# Lamp_Logic_Board_40_BRAIN.net
KiCad netlist of a schematic drawn in EAGLE
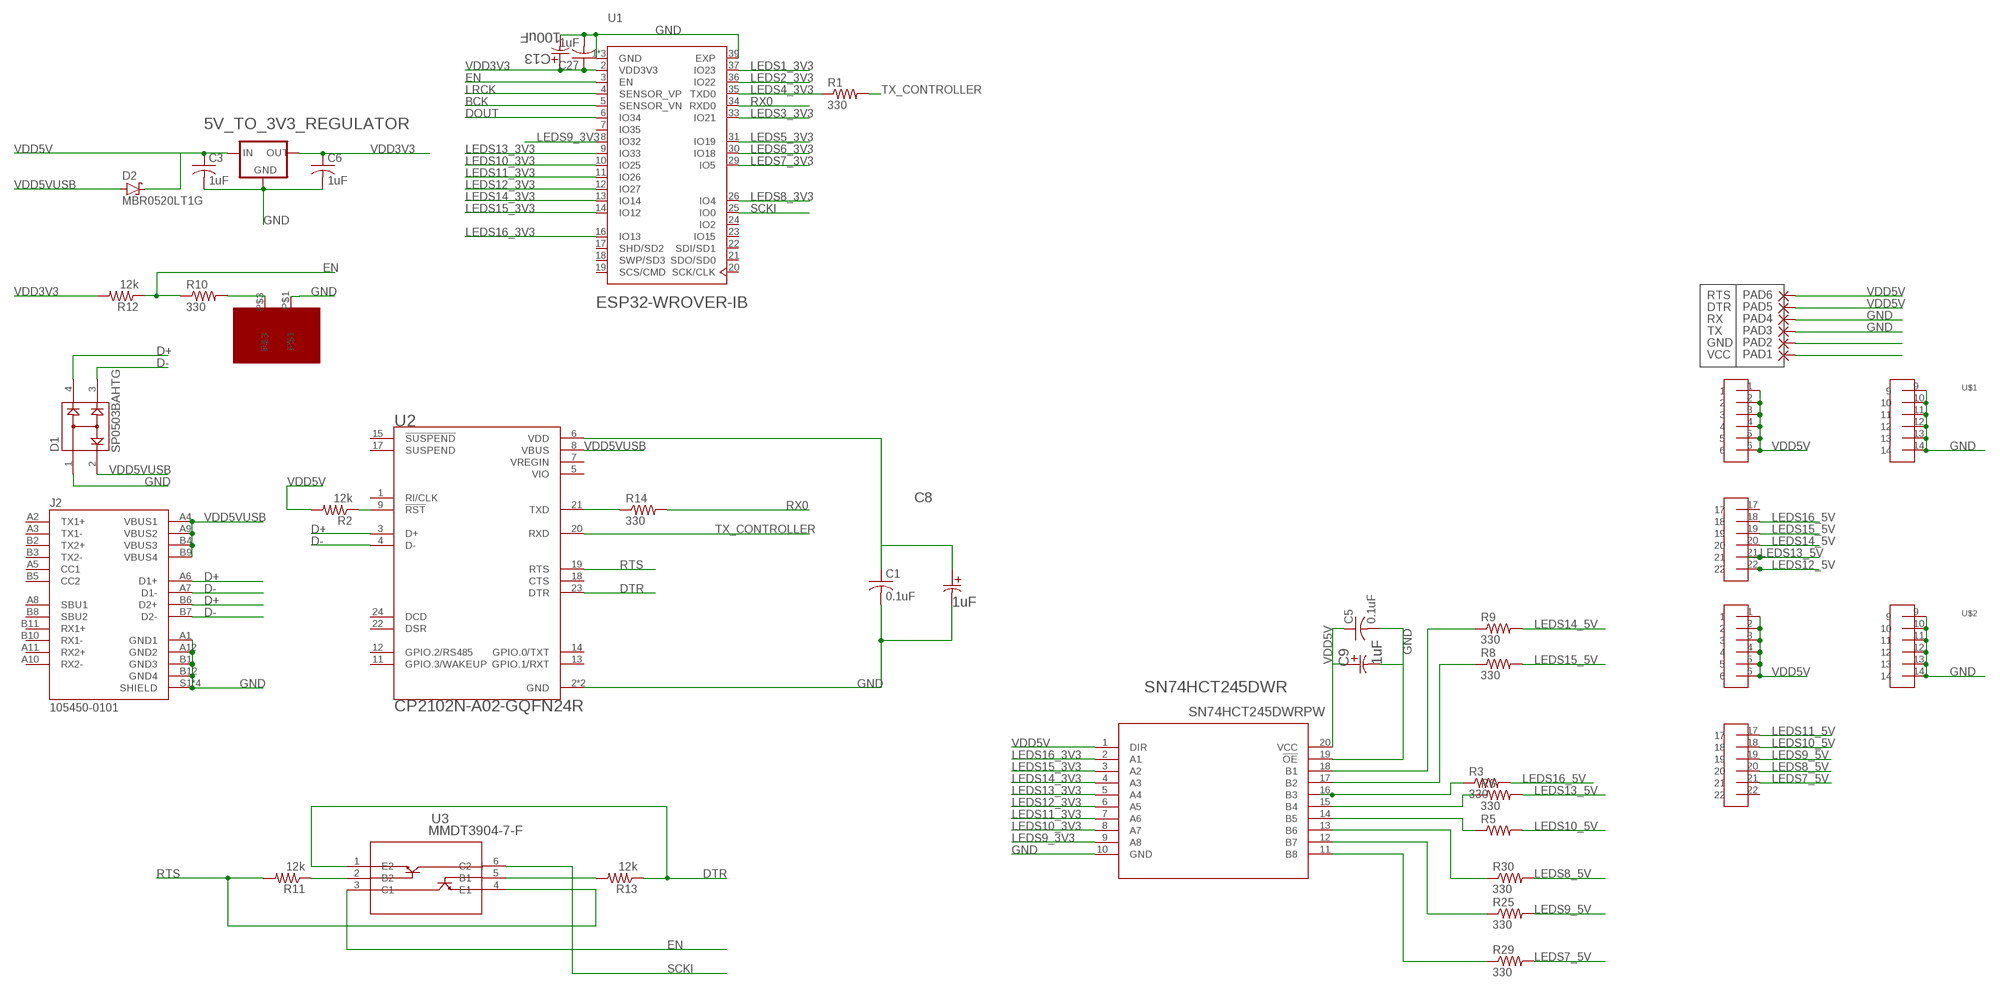
[diagram p0: schematic, sheet 1]

(export (version "E")
  (design (tool "Eeschema 10.0.6"))
  (components
    (comp (ref "5V_TO_3V3_REGULATOR")
      (value "LM1117MP-1.8")
      (footprint "eagle-import:SOT223")
      (fields (field (name "MF") "Texas Instruments"))
      (libsource (lib "eagle-import") (part "LM1117?-MP1.8"))
    )
    (comp (ref "C1")
      (value "0.1uF")
      (footprint "eagle-import:C0402")
      (libsource (lib "eagle-import") (part "C-USC0402"))
    )
    (comp (ref "C3")
      (value "1uF")
      (footprint "eagle-import:C0402")
      (libsource (lib "eagle-import") (part "C-USC0402"))
    )
    (comp (ref "C5")
      (value "0.1uF")
      (footprint "eagle-import:C0805")
      (libsource (lib "eagle-import") (part "C-USC0805"))
    )
    (comp (ref "C6")
      (value "1uF")
      (footprint "eagle-import:C0402")
      (libsource (lib "eagle-import") (part "C-USC0402"))
    )
    (comp (ref "C8")
      (value "1uF")
      (footprint "eagle-import:CAP_EEFC_B")
      (fields (field (name "MANUFACTURER_PART_NUMBER") "EEEFC1V1R0R"))
      (libsource (lib "eagle-import") (part "EEEFC1V1R0R"))
    )
    (comp (ref "C9")
      (value "1uF")
      (footprint "eagle-import:CAP_EEFC_B")
      (fields (field (name "MANUFACTURER_PART_NUMBER") "EEEFC1V1R0R"))
      (libsource (lib "eagle-import") (part "EEEFC1V1R0R"))
    )
    (comp (ref "C13")
      (value "100uF")
      (footprint "eagle-import:CAP_EEFC_B")
      (fields (field (name "MANUFACTURER_PART_NUMBER") "EEEFC1V1R0R"))
      (libsource (lib "eagle-import") (part "EEEFC1V1R0R"))
    )
    (comp (ref "C27")
      (value "1uF")
      (footprint "eagle-import:C0402")
      (libsource (lib "eagle-import") (part "C-USC0402"))
    )
    (comp (ref "D1")
      (value "SP0503BAHTG")
      (footprint "eagle-import:SOT143")
      (fields (field (name "DIGI-KEY_PART_NUMBER") "F2715CT-ND") (field (name "MF") "Littelfuse Inc."))
      (libsource (lib "eagle-import") (part "SP0503BAHTG"))
    )
    (comp (ref "D2")
      (value "MBR0520LT1G")
      (footprint "eagle-import:SOD-123")
      (fields
        (field (name "DIGIKEY_PART_NUMBER") "MBR0520LT1GOSTR-ND")
        (field (name "MANUFACTURER") "ON Semiconductor")
        (field (name "CREATED_BY") "PCBLayout.com")
      )
      (libsource (lib "eagle-import") (part "MBR0520LT1G"))
    )
    (comp (ref "J2")
      (value "105450-0101")
      (footprint "eagle-import:MOLEX_105450-0101")
      (fields
        (field (name "DIGI-KEY_PART_NUMBER") "WM12856CT-ND")
        (field (name "MF") "Molex")
        (field (name "MP") "1054500101")
      )
      (libsource (lib "eagle-import") (part "105450-0101"))
    )
    (comp (ref "PAD1")
      (value "VCC")
      (footprint "eagle-import:SMD1,27-2,54")
      (libsource (lib "eagle-import") (part "WIREPADSMD1,27-254"))
    )
    (comp (ref "PAD2")
      (value "GND")
      (footprint "eagle-import:SMD1,27-2,54")
      (libsource (lib "eagle-import") (part "WIREPADSMD1,27-254"))
    )
    (comp (ref "PAD3")
      (value "TX")
      (footprint "eagle-import:SMD1,27-2,54")
      (libsource (lib "eagle-import") (part "WIREPADSMD1,27-254"))
    )
    (comp (ref "PAD4")
      (value "RX")
      (footprint "eagle-import:SMD1,27-2,54")
      (libsource (lib "eagle-import") (part "WIREPADSMD1,27-254"))
    )
    (comp (ref "PAD5")
      (value "DTR")
      (footprint "eagle-import:SMD1,27-2,54")
      (libsource (lib "eagle-import") (part "WIREPADSMD1,27-254"))
    )
    (comp (ref "PAD6")
      (value "RTS")
      (footprint "eagle-import:SMD1,27-2,54")
      (libsource (lib "eagle-import") (part "WIREPADSMD1,27-254"))
    )
    (comp (ref "R1")
      (value "330")
      (footprint "eagle-import:RES_0603")
      (fields
        (field (name "DIGIKEY_PART_NUMBER") "311-0.0GRTR-ND")
        (field (name "MANUFACTURER") "Yageo")
        (field (name "MPN") "RC0603JR-070RL")
        (field (name "CREATED_BY") "PCBLayout.com")
      )
      (libsource (lib "eagle-import") (part "RC0603JR-070RL"))
    )
    (comp (ref "R2")
      (value "12k")
      (footprint "eagle-import:RES_0603")
      (fields
        (field (name "DIGIKEY_PART_NUMBER") "311-0.0GRTR-ND")
        (field (name "MANUFACTURER") "Yageo")
        (field (name "MPN") "RC0603JR-070RL")
        (field (name "CREATED_BY") "PCBLayout.com")
      )
      (libsource (lib "eagle-import") (part "RC0603JR-070RL"))
    )
    (comp (ref "R3")
      (value "330")
      (footprint "eagle-import:RES_0603")
      (fields
        (field (name "DIGIKEY_PART_NUMBER") "311-0.0GRTR-ND")
        (field (name "MANUFACTURER") "Yageo")
        (field (name "MPN") "RC0603JR-070RL")
        (field (name "CREATED_BY") "PCBLayout.com")
      )
      (libsource (lib "eagle-import") (part "RC0603JR-070RL"))
    )
    (comp (ref "R5")
      (value "330")
      (footprint "eagle-import:RES_0603")
      (fields
        (field (name "DIGIKEY_PART_NUMBER") "311-0.0GRTR-ND")
        (field (name "MANUFACTURER") "Yageo")
        (field (name "MPN") "RC0603JR-070RL")
        (field (name "CREATED_BY") "PCBLayout.com")
      )
      (libsource (lib "eagle-import") (part "RC0603JR-070RL"))
    )
    (comp (ref "R6")
      (value "330")
      (footprint "eagle-import:RES_0603")
      (fields
        (field (name "DIGIKEY_PART_NUMBER") "311-0.0GRTR-ND")
        (field (name "MANUFACTURER") "Yageo")
        (field (name "MPN") "RC0603JR-070RL")
        (field (name "CREATED_BY") "PCBLayout.com")
      )
      (libsource (lib "eagle-import") (part "RC0603JR-070RL"))
    )
    (comp (ref "R8")
      (value "330")
      (footprint "eagle-import:RES_0603")
      (fields
        (field (name "DIGIKEY_PART_NUMBER") "311-0.0GRTR-ND")
        (field (name "MANUFACTURER") "Yageo")
        (field (name "MPN") "RC0603JR-070RL")
        (field (name "CREATED_BY") "PCBLayout.com")
      )
      (libsource (lib "eagle-import") (part "RC0603JR-070RL"))
    )
    (comp (ref "R9")
      (value "330")
      (footprint "eagle-import:RES_0603")
      (fields
        (field (name "DIGIKEY_PART_NUMBER") "311-0.0GRTR-ND")
        (field (name "MANUFACTURER") "Yageo")
        (field (name "MPN") "RC0603JR-070RL")
        (field (name "CREATED_BY") "PCBLayout.com")
      )
      (libsource (lib "eagle-import") (part "RC0603JR-070RL"))
    )
    (comp (ref "R10")
      (value "330")
      (footprint "eagle-import:RES_0603")
      (fields
        (field (name "DIGIKEY_PART_NUMBER") "311-0.0GRTR-ND")
        (field (name "MANUFACTURER") "Yageo")
        (field (name "MPN") "RC0603JR-070RL")
        (field (name "CREATED_BY") "PCBLayout.com")
      )
      (libsource (lib "eagle-import") (part "RC0603JR-070RL"))
    )
    (comp (ref "R11")
      (value "12k")
      (footprint "eagle-import:RES_0603")
      (fields
        (field (name "DIGIKEY_PART_NUMBER") "311-0.0GRTR-ND")
        (field (name "MANUFACTURER") "Yageo")
        (field (name "MPN") "RC0603JR-070RL")
        (field (name "CREATED_BY") "PCBLayout.com")
      )
      (libsource (lib "eagle-import") (part "RC0603JR-070RL"))
    )
    (comp (ref "R12")
      (value "12k")
      (footprint "eagle-import:RES_0603")
      (fields
        (field (name "DIGIKEY_PART_NUMBER") "311-0.0GRTR-ND")
        (field (name "MANUFACTURER") "Yageo")
        (field (name "MPN") "RC0603JR-070RL")
        (field (name "CREATED_BY") "PCBLayout.com")
      )
      (libsource (lib "eagle-import") (part "RC0603JR-070RL"))
    )
    (comp (ref "R13")
      (value "12k")
      (footprint "eagle-import:RES_0603")
      (fields
        (field (name "DIGIKEY_PART_NUMBER") "311-0.0GRTR-ND")
        (field (name "MANUFACTURER") "Yageo")
        (field (name "MPN") "RC0603JR-070RL")
        (field (name "CREATED_BY") "PCBLayout.com")
      )
      (libsource (lib "eagle-import") (part "RC0603JR-070RL"))
    )
    (comp (ref "R14")
      (value "330")
      (footprint "eagle-import:RES_0603")
      (fields
        (field (name "DIGIKEY_PART_NUMBER") "311-0.0GRTR-ND")
        (field (name "MANUFACTURER") "Yageo")
        (field (name "MPN") "RC0603JR-070RL")
        (field (name "CREATED_BY") "PCBLayout.com")
      )
      (libsource (lib "eagle-import") (part "RC0603JR-070RL"))
    )
    (comp (ref "R25")
      (value "330")
      (footprint "eagle-import:RES_0603")
      (fields
        (field (name "DIGIKEY_PART_NUMBER") "311-0.0GRTR-ND")
        (field (name "MANUFACTURER") "Yageo")
        (field (name "MPN") "RC0603JR-070RL")
        (field (name "CREATED_BY") "PCBLayout.com")
      )
      (libsource (lib "eagle-import") (part "RC0603JR-070RL"))
    )
    (comp (ref "R29")
      (value "330")
      (footprint "eagle-import:RES_0603")
      (fields
        (field (name "DIGIKEY_PART_NUMBER") "311-0.0GRTR-ND")
        (field (name "MANUFACTURER") "Yageo")
        (field (name "MPN") "RC0603JR-070RL")
        (field (name "CREATED_BY") "PCBLayout.com")
      )
      (libsource (lib "eagle-import") (part "RC0603JR-070RL"))
    )
    (comp (ref "R30")
      (value "330")
      (footprint "eagle-import:RES_0603")
      (fields
        (field (name "DIGIKEY_PART_NUMBER") "311-0.0GRTR-ND")
        (field (name "MANUFACTURER") "Yageo")
        (field (name "MPN") "RC0603JR-070RL")
        (field (name "CREATED_BY") "PCBLayout.com")
      )
      (libsource (lib "eagle-import") (part "RC0603JR-070RL"))
    )
    (comp (ref "SN74HCT245DWR")
      (value "SN74HCT245DWRPW")
      (footprint "eagle-import:PW")
      (libsource (lib "eagle-import") (part "SN74HCT245DWRPW"))
    )
    (comp (ref "U$1")
      (value "3X8PINHEAD")
      (footprint "eagle-import:3X8PINHEAD")
      (libsource (lib "eagle-import") (part "3X8PINHEAD"))
    )
    (comp (ref "U$2")
      (value "3X8PINHEAD")
      (footprint "eagle-import:3X8PINHEAD")
      (libsource (lib "eagle-import") (part "3X8PINHEAD"))
    )
    (comp (ref "U$7")
      (value "TL1014BF160QG")
      (footprint "eagle-import:TL1014BF160QG")
      (libsource (lib "eagle-import") (part "TL1014BF160QG"))
    )
    (comp (ref "U1")
      (value "ESP32-WROVER-IB")
      (footprint "eagle-import:XCVR_ESP32-WROVER-I")
      (fields (field (name "MF") "Espressif Systems") (field (name "MP") "ESP32-WROVER-I"))
      (libsource (lib "eagle-import") (part "ESP32-WROVER-I"))
    )
    (comp (ref "U2")
      (value "CP2102N-A02-GQFN24R")
      (footprint "eagle-import:SILABS_CP2102N-A02-GQFN24R")
      (libsource (lib "eagle-import") (part "CP2102N-A02-GQFN24R"))
    )
    (comp (ref "U3")
      (value "MMDT3904-7-F")
      (footprint "eagle-import:SOT-363")
      (fields (field (name "MANUFACTURER_PART_NUMBER") "MMDT39047F"))
      (libsource (lib "eagle-import") (part "MMDT3904-7-F"))
    )
  )
  (nets
    (net (code "1") (name "BCK") (class "Default")
      (node (ref "U1") (pin "5") (pinfunction "SENSOR_VN_5") (pintype "input"))
    )
    (net (code "2") (name "D+") (class "Default")
      (node (ref "D1") (pin "4") (pinfunction "4_4") (pintype "passive"))
      (node (ref "J2") (pin "A6") (pinfunction "D1+_A6") (pintype "passive"))
      (node (ref "J2") (pin "B6") (pinfunction "D2+_B6") (pintype "passive"))
      (node (ref "U2") (pin "3") (pinfunction "D+_3") (pintype "bidirectional"))
    )
    (net (code "3") (name "D-") (class "Default")
      (node (ref "D1") (pin "3") (pinfunction "3_3") (pintype "passive"))
      (node (ref "J2") (pin "A7") (pinfunction "D1-_A7") (pintype "passive"))
      (node (ref "J2") (pin "B7") (pinfunction "D2-_B7") (pintype "passive"))
      (node (ref "U2") (pin "4") (pinfunction "D-_4") (pintype "bidirectional"))
    )
    (net (code "4") (name "DOUT") (class "Default")
      (node (ref "U1") (pin "6") (pinfunction "IO34_6") (pintype "input"))
    )
    (net (code "5") (name "DTR") (class "Default")
      (node (ref "R13") (pin "1") (pinfunction "1_1") (pintype "passive"))
      (node (ref "U2") (pin "23") (pinfunction "DTR_23") (pintype "bidirectional"))
      (node (ref "U3") (pin "1") (pinfunction "E2_1") (pintype "passive"))
    )
    (net (code "6") (name "EN") (class "Default")
      (node (ref "R10") (pin "1") (pinfunction "1_1") (pintype "passive"))
      (node (ref "R12") (pin "1") (pinfunction "1_1") (pintype "passive"))
      (node (ref "U1") (pin "3") (pinfunction "EN_3") (pintype "input"))
      (node (ref "U3") (pin "3") (pinfunction "C1_3") (pintype "passive"))
    )
    (net (code "7") (name "GND") (class "Default")
      (node (ref "5V_TO_3V3_REGULATOR") (pin "1") (pinfunction "GND_1") (pintype "input"))
      (node (ref "C1") (pin "2") (pinfunction "2_2") (pintype "passive"))
      (node (ref "C13") (pin "2") (pinfunction "2_2") (pintype "passive"))
      (node (ref "C27") (pin "2") (pinfunction "2_2") (pintype "passive"))
      (node (ref "C3") (pin "2") (pinfunction "2_2") (pintype "passive"))
      (node (ref "C5") (pin "2") (pinfunction "2_2") (pintype "passive"))
      (node (ref "C6") (pin "2") (pinfunction "2_2") (pintype "passive"))
      (node (ref "C8") (pin "2") (pinfunction "2_2") (pintype "passive"))
      (node (ref "C9") (pin "2") (pinfunction "2_2") (pintype "passive"))
      (node (ref "D1") (pin "1") (pinfunction "1_1") (pintype "passive"))
      (node (ref "J2") (pin "A1") (pinfunction "GND1_A1") (pintype "passive"))
      (node (ref "J2") (pin "A12") (pinfunction "GND2_A12") (pintype "passive"))
      (node (ref "J2") (pin "B1") (pinfunction "GND3_B1") (pintype "passive"))
      (node (ref "J2") (pin "B12") (pinfunction "GND4_B12") (pintype "passive"))
      (node (ref "J2") (pin "S1") (pinfunction "SHIELD_S1") (pintype "passive"))
      (node (ref "J2") (pin "S2") (pinfunction "SHIELD_S2") (pintype "passive"))
      (node (ref "J2") (pin "S3") (pinfunction "SHIELD_S3") (pintype "passive"))
      (node (ref "J2") (pin "S4") (pinfunction "SHIELD_S4") (pintype "passive"))
      (node (ref "PAD3") (pin "1") (pinfunction "P_1") (pintype "passive"))
      (node (ref "PAD4") (pin "1") (pinfunction "P_1") (pintype "passive"))
      (node (ref "SN74HCT245DWR") (pin "10") (pinfunction "GND_10") (pintype "power_in"))
      (node (ref "SN74HCT245DWR") (pin "19") (pinfunction "~{OE}_19") (pintype "input"))
      (node (ref "U$1") (pin "10") (pinfunction "10_10") (pintype "bidirectional"))
      (node (ref "U$1") (pin "11") (pinfunction "11_11") (pintype "bidirectional"))
      (node (ref "U$1") (pin "12") (pinfunction "12_12") (pintype "bidirectional"))
      (node (ref "U$1") (pin "13") (pinfunction "13_13") (pintype "bidirectional"))
      (node (ref "U$1") (pin "14") (pinfunction "14_14") (pintype "bidirectional"))
      (node (ref "U$1") (pin "9") (pinfunction "9_9") (pintype "bidirectional"))
      (node (ref "U$2") (pin "10") (pinfunction "10_10") (pintype "bidirectional"))
      (node (ref "U$2") (pin "11") (pinfunction "11_11") (pintype "bidirectional"))
      (node (ref "U$2") (pin "12") (pinfunction "12_12") (pintype "bidirectional"))
      (node (ref "U$2") (pin "13") (pinfunction "13_13") (pintype "bidirectional"))
      (node (ref "U$2") (pin "14") (pinfunction "14_14") (pintype "bidirectional"))
      (node (ref "U$2") (pin "9") (pinfunction "9_9") (pintype "bidirectional"))
      (node (ref "U$7") (pin "P$1") (pinfunction "P$1_P$1") (pintype "bidirectional"))
      (node (ref "U1") (pin "1") (pinfunction "GND_1") (pintype "power_in"))
      (node (ref "U1") (pin "15") (pinfunction "GND_15") (pintype "power_in"))
      (node (ref "U1") (pin "38") (pinfunction "GND_38") (pintype "power_in"))
      (node (ref "U1") (pin "39") (pinfunction "EXP_39") (pintype "power_in"))
      (node (ref "U2") (pin "2") (pinfunction "GND_2") (pintype "power_in"))
      (node (ref "U2") (pin "25") (pinfunction "GND_25") (pintype "power_in"))
    )
    (net (code "8") (name "LEDS1_3V3") (class "Default")
      (node (ref "U1") (pin "37") (pinfunction "IO23_37") (pintype "bidirectional"))
    )
    (net (code "9") (name "LEDS2_3V3") (class "Default")
      (node (ref "U1") (pin "36") (pinfunction "IO22_36") (pintype "bidirectional"))
    )
    (net (code "10") (name "LEDS3_3V3") (class "Default")
      (node (ref "U1") (pin "33") (pinfunction "IO21_33") (pintype "bidirectional"))
    )
    (net (code "11") (name "LEDS4_3V3") (class "Default")
      (node (ref "R1") (pin "1") (pinfunction "1_1") (pintype "passive"))
      (node (ref "U1") (pin "35") (pinfunction "TXD0_35") (pintype "bidirectional"))
    )
    (net (code "12") (name "LEDS5_3V3") (class "Default")
      (node (ref "U1") (pin "31") (pinfunction "IO19_31") (pintype "bidirectional"))
    )
    (net (code "13") (name "LEDS6_3V3") (class "Default")
      (node (ref "U1") (pin "30") (pinfunction "IO18_30") (pintype "bidirectional"))
    )
    (net (code "14") (name "LEDS7_3V3") (class "Default")
      (node (ref "U1") (pin "29") (pinfunction "IO5_29") (pintype "bidirectional"))
    )
    (net (code "15") (name "LEDS7_5V") (class "Default")
      (node (ref "R29") (pin "2") (pinfunction "2_2") (pintype "passive"))
      (node (ref "U$2") (pin "21") (pinfunction "21_21") (pintype "bidirectional"))
    )
    (net (code "16") (name "LEDS8_3V3") (class "Default")
      (node (ref "U1") (pin "26") (pinfunction "IO4_26") (pintype "bidirectional"))
    )
    (net (code "17") (name "LEDS8_5V") (class "Default")
      (node (ref "R30") (pin "2") (pinfunction "2_2") (pintype "passive"))
      (node (ref "U$2") (pin "20") (pinfunction "20_20") (pintype "bidirectional"))
    )
    (net (code "18") (name "LEDS9_3V3") (class "Default")
      (node (ref "SN74HCT245DWR") (pin "9") (pinfunction "A8_9") (pintype "bidirectional"))
      (node (ref "U1") (pin "8") (pinfunction "IO32_8") (pintype "bidirectional"))
    )
    (net (code "19") (name "LEDS9_5V") (class "Default")
      (node (ref "R25") (pin "2") (pinfunction "2_2") (pintype "passive"))
      (node (ref "U$2") (pin "19") (pinfunction "19_19") (pintype "bidirectional"))
    )
    (net (code "20") (name "LEDS10_3V3") (class "Default")
      (node (ref "SN74HCT245DWR") (pin "8") (pinfunction "A7_8") (pintype "bidirectional"))
      (node (ref "U1") (pin "10") (pinfunction "IO25_10") (pintype "bidirectional"))
    )
    (net (code "21") (name "LEDS10_5V") (class "Default")
      (node (ref "R5") (pin "2") (pinfunction "2_2") (pintype "passive"))
      (node (ref "U$2") (pin "18") (pinfunction "18_18") (pintype "bidirectional"))
    )
    (net (code "22") (name "LEDS11_3V3") (class "Default")
      (node (ref "SN74HCT245DWR") (pin "7") (pinfunction "A6_7") (pintype "bidirectional"))
      (node (ref "U1") (pin "11") (pinfunction "IO26_11") (pintype "bidirectional"))
    )
    (net (code "23") (name "LEDS11_5V") (class "Default")
      (node (ref "U$2") (pin "17") (pinfunction "17_17") (pintype "bidirectional"))
    )
    (net (code "24") (name "LEDS12_3V3") (class "Default")
      (node (ref "SN74HCT245DWR") (pin "6") (pinfunction "A5_6") (pintype "bidirectional"))
      (node (ref "U1") (pin "12") (pinfunction "IO27_12") (pintype "bidirectional"))
    )
    (net (code "25") (name "LEDS12_5V") (class "Default")
      (node (ref "U$1") (pin "22") (pinfunction "22_22") (pintype "bidirectional"))
    )
    (net (code "26") (name "LEDS13_3V3") (class "Default")
      (node (ref "SN74HCT245DWR") (pin "5") (pinfunction "A4_5") (pintype "bidirectional"))
      (node (ref "U1") (pin "9") (pinfunction "IO33_9") (pintype "bidirectional"))
    )
    (net (code "27") (name "LEDS13_5V") (class "Default")
      (node (ref "R6") (pin "2") (pinfunction "2_2") (pintype "passive"))
      (node (ref "U$1") (pin "21") (pinfunction "21_21") (pintype "bidirectional"))
    )
    (net (code "28") (name "LEDS14_3V3") (class "Default")
      (node (ref "SN74HCT245DWR") (pin "4") (pinfunction "A3_4") (pintype "bidirectional"))
      (node (ref "U1") (pin "13") (pinfunction "IO14_13") (pintype "bidirectional"))
    )
    (net (code "29") (name "LEDS14_5V") (class "Default")
      (node (ref "R9") (pin "2") (pinfunction "2_2") (pintype "passive"))
      (node (ref "U$1") (pin "20") (pinfunction "20_20") (pintype "bidirectional"))
    )
    (net (code "30") (name "LEDS15_3V3") (class "Default")
      (node (ref "SN74HCT245DWR") (pin "3") (pinfunction "A2_3") (pintype "bidirectional"))
      (node (ref "U1") (pin "14") (pinfunction "IO12_14") (pintype "bidirectional"))
    )
    (net (code "31") (name "LEDS15_5V") (class "Default")
      (node (ref "R8") (pin "2") (pinfunction "2_2") (pintype "passive"))
      (node (ref "U$1") (pin "19") (pinfunction "19_19") (pintype "bidirectional"))
    )
    (net (code "32") (name "LEDS16_3V3") (class "Default")
      (node (ref "SN74HCT245DWR") (pin "2") (pinfunction "A1_2") (pintype "bidirectional"))
      (node (ref "U1") (pin "16") (pinfunction "IO13_16") (pintype "bidirectional"))
    )
    (net (code "33") (name "LEDS16_5V") (class "Default")
      (node (ref "R3") (pin "2") (pinfunction "2_2") (pintype "passive"))
      (node (ref "U$1") (pin "18") (pinfunction "18_18") (pintype "bidirectional"))
    )
    (net (code "34") (name "LRCK") (class "Default")
      (node (ref "U1") (pin "4") (pinfunction "SENSOR_VP_4") (pintype "input"))
    )
    (net (code "35") (name "Net-(R10-Pad2)") (class "Default")
      (node (ref "R10") (pin "2") (pinfunction "2_2") (pintype "passive"))
      (node (ref "U$7") (pin "P$3") (pinfunction "P$3_P$3") (pintype "bidirectional"))
    )
    (net (code "36") (name "Net-(SN74HCT245DWR-B1)") (class "Default")
      (node (ref "R9") (pin "1") (pinfunction "1_1") (pintype "passive"))
      (node (ref "SN74HCT245DWR") (pin "18") (pinfunction "B1_18") (pintype "bidirectional"))
    )
    (net (code "37") (name "Net-(SN74HCT245DWR-B2)") (class "Default")
      (node (ref "R8") (pin "1") (pinfunction "1_1") (pintype "passive"))
      (node (ref "SN74HCT245DWR") (pin "17") (pinfunction "B2_17") (pintype "bidirectional"))
    )
    (net (code "38") (name "Net-(SN74HCT245DWR-B3)") (class "Default")
      (node (ref "R3") (pin "1") (pinfunction "1_1") (pintype "passive"))
      (node (ref "SN74HCT245DWR") (pin "16") (pinfunction "B3_16") (pintype "bidirectional"))
    )
    (net (code "39") (name "Net-(SN74HCT245DWR-B4)") (class "Default")
      (node (ref "R6") (pin "1") (pinfunction "1_1") (pintype "passive"))
      (node (ref "SN74HCT245DWR") (pin "15") (pinfunction "B4_15") (pintype "bidirectional"))
    )
    (net (code "40") (name "Net-(SN74HCT245DWR-B5)") (class "Default")
      (node (ref "R5") (pin "1") (pinfunction "1_1") (pintype "passive"))
      (node (ref "SN74HCT245DWR") (pin "14") (pinfunction "B5_14") (pintype "bidirectional"))
    )
    (net (code "41") (name "Net-(SN74HCT245DWR-B6)") (class "Default")
      (node (ref "R30") (pin "1") (pinfunction "1_1") (pintype "passive"))
      (node (ref "SN74HCT245DWR") (pin "13") (pinfunction "B6_13") (pintype "bidirectional"))
    )
    (net (code "42") (name "Net-(SN74HCT245DWR-B7)") (class "Default")
      (node (ref "R25") (pin "1") (pinfunction "1_1") (pintype "passive"))
      (node (ref "SN74HCT245DWR") (pin "12") (pinfunction "B7_12") (pintype "bidirectional"))
    )
    (net (code "43") (name "Net-(SN74HCT245DWR-B8)") (class "Default")
      (node (ref "R29") (pin "1") (pinfunction "1_1") (pintype "passive"))
      (node (ref "SN74HCT245DWR") (pin "11") (pinfunction "B8_11") (pintype "bidirectional"))
    )
    (net (code "44") (name "Net-(U2-TXD)") (class "Default")
      (node (ref "R14") (pin "1") (pinfunction "1_1") (pintype "passive"))
      (node (ref "U2") (pin "21") (pinfunction "TXD_21") (pintype "output"))
    )
    (net (code "45") (name "Net-(U2-VDD)") (class "Default")
      (node (ref "C1") (pin "1") (pinfunction "1_1") (pintype "passive"))
      (node (ref "C8") (pin "1") (pinfunction "1_1") (pintype "passive"))
      (node (ref "U2") (pin "6") (pinfunction "VDD_6") (pintype "power_in"))
    )
    (net (code "46") (name "Net-(U2-~{RST})") (class "Default")
      (node (ref "R2") (pin "1") (pinfunction "1_1") (pintype "passive"))
      (node (ref "U2") (pin "9") (pinfunction "~{RST}_9") (pintype "input"))
    )
    (net (code "47") (name "Net-(U3-B1)") (class "Default")
      (node (ref "R13") (pin "2") (pinfunction "2_2") (pintype "passive"))
      (node (ref "U3") (pin "5") (pinfunction "B1_5") (pintype "passive"))
    )
    (net (code "48") (name "Net-(U3-B2)") (class "Default")
      (node (ref "R11") (pin "1") (pinfunction "1_1") (pintype "passive"))
      (node (ref "U3") (pin "2") (pinfunction "B2_2") (pintype "passive"))
    )
    (net (code "49") (name "RTS") (class "Default")
      (node (ref "R11") (pin "2") (pinfunction "2_2") (pintype "passive"))
      (node (ref "U2") (pin "19") (pinfunction "RTS_19") (pintype "output"))
      (node (ref "U3") (pin "4") (pinfunction "E1_4") (pintype "passive"))
    )
    (net (code "50") (name "RX0") (class "Default")
      (node (ref "R14") (pin "2") (pinfunction "2_2") (pintype "passive"))
      (node (ref "U1") (pin "34") (pinfunction "RXD0_34") (pintype "bidirectional"))
    )
    (net (code "51") (name "SCKI") (class "Default")
      (node (ref "U1") (pin "25") (pinfunction "IO0_25") (pintype "bidirectional"))
      (node (ref "U3") (pin "6") (pinfunction "C2_6") (pintype "passive"))
    )
    (net (code "52") (name "TX_CONTROLLER") (class "Default")
      (node (ref "R1") (pin "2") (pinfunction "2_2") (pintype "passive"))
      (node (ref "U2") (pin "20") (pinfunction "RXD_20") (pintype "input"))
    )
    (net (code "53") (name "VDD3V3") (class "Default")
      (node (ref "5V_TO_3V3_REGULATOR") (pin "2") (pinfunction "OUT_2") (pintype "passive"))
      (node (ref "5V_TO_3V3_REGULATOR") (pin "4") (pinfunction "OUT_4") (pintype "passive"))
      (node (ref "C13") (pin "1") (pinfunction "1_1") (pintype "passive"))
      (node (ref "C27") (pin "1") (pinfunction "1_1") (pintype "passive"))
      (node (ref "C6") (pin "1") (pinfunction "1_1") (pintype "passive"))
      (node (ref "R12") (pin "2") (pinfunction "2_2") (pintype "passive"))
      (node (ref "U1") (pin "2") (pinfunction "VDD3V3_2") (pintype "power_in"))
    )
    (net (code "54") (name "VDD5V") (class "Default")
      (node (ref "5V_TO_3V3_REGULATOR") (pin "3") (pinfunction "IN_3") (pintype "input"))
      (node (ref "C3") (pin "1") (pinfunction "1_1") (pintype "passive"))
      (node (ref "C5") (pin "1") (pinfunction "1_1") (pintype "passive"))
      (node (ref "C9") (pin "1") (pinfunction "1_1") (pintype "passive"))
      (node (ref "D2") (pin "C") (pinfunction "C_C") (pintype "passive"))
      (node (ref "PAD5") (pin "1") (pinfunction "P_1") (pintype "passive"))
      (node (ref "PAD6") (pin "1") (pinfunction "P_1") (pintype "passive"))
      (node (ref "R2") (pin "2") (pinfunction "2_2") (pintype "passive"))
      (node (ref "SN74HCT245DWR") (pin "1") (pinfunction "DIR_1") (pintype "input"))
      (node (ref "SN74HCT245DWR") (pin "20") (pinfunction "VCC_20") (pintype "power_in"))
      (node (ref "U$1") (pin "1") (pinfunction "1_1") (pintype "bidirectional"))
      (node (ref "U$1") (pin "2") (pinfunction "2_2") (pintype "bidirectional"))
      (node (ref "U$1") (pin "3") (pinfunction "3_3") (pintype "bidirectional"))
      (node (ref "U$1") (pin "4") (pinfunction "4_4") (pintype "bidirectional"))
      (node (ref "U$1") (pin "5") (pinfunction "5_5") (pintype "bidirectional"))
      (node (ref "U$1") (pin "6") (pinfunction "6_6") (pintype "bidirectional"))
      (node (ref "U$2") (pin "1") (pinfunction "1_1") (pintype "bidirectional"))
      (node (ref "U$2") (pin "2") (pinfunction "2_2") (pintype "bidirectional"))
      (node (ref "U$2") (pin "3") (pinfunction "3_3") (pintype "bidirectional"))
      (node (ref "U$2") (pin "4") (pinfunction "4_4") (pintype "bidirectional"))
      (node (ref "U$2") (pin "5") (pinfunction "5_5") (pintype "bidirectional"))
      (node (ref "U$2") (pin "6") (pinfunction "6_6") (pintype "bidirectional"))
    )
    (net (code "55") (name "VDD5VUSB") (class "Default")
      (node (ref "D1") (pin "2") (pinfunction "2_2") (pintype "passive"))
      (node (ref "D2") (pin "A") (pinfunction "A_A") (pintype "passive"))
      (node (ref "J2") (pin "A4") (pinfunction "VBUS1_A4") (pintype "passive"))
      (node (ref "J2") (pin "A9") (pinfunction "VBUS2_A9") (pintype "passive"))
      (node (ref "J2") (pin "B4") (pinfunction "VBUS3_B4") (pintype "passive"))
      (node (ref "J2") (pin "B9") (pinfunction "VBUS4_B9") (pintype "passive"))
      (node (ref "U2") (pin "8") (pinfunction "VBUS_8") (pintype "power_in"))
    )
    (net (code "56") (name "VREGIN") (class "Default")
      (node (ref "U2") (pin "7") (pinfunction "VREGIN_7") (pintype "power_in"))
    )
    (net (code "57") (name "unconnected-(J2-CC1-PadA5)") (class "Default")
      (node (ref "J2") (pin "A5") (pinfunction "CC1_A5") (pintype "passive"))
    )
    (net (code "58") (name "unconnected-(J2-CC2-PadB5)") (class "Default")
      (node (ref "J2") (pin "B5") (pinfunction "CC2_B5") (pintype "passive"))
    )
    (net (code "59") (name "unconnected-(J2-RX1+-PadB11)") (class "Default")
      (node (ref "J2") (pin "B11") (pinfunction "RX1+_B11") (pintype "passive"))
    )
    (net (code "60") (name "unconnected-(J2-RX1--PadB10)") (class "Default")
      (node (ref "J2") (pin "B10") (pinfunction "RX1-_B10") (pintype "passive"))
    )
    (net (code "61") (name "unconnected-(J2-RX2+-PadA11)") (class "Default")
      (node (ref "J2") (pin "A11") (pinfunction "RX2+_A11") (pintype "passive"))
    )
    (net (code "62") (name "unconnected-(J2-RX2--PadA10)") (class "Default")
      (node (ref "J2") (pin "A10") (pinfunction "RX2-_A10") (pintype "passive"))
    )
    (net (code "63") (name "unconnected-(J2-SBU1-PadA8)") (class "Default")
      (node (ref "J2") (pin "A8") (pinfunction "SBU1_A8") (pintype "passive"))
    )
    (net (code "64") (name "unconnected-(J2-SBU2-PadB8)") (class "Default")
      (node (ref "J2") (pin "B8") (pinfunction "SBU2_B8") (pintype "passive"))
    )
    (net (code "65") (name "unconnected-(J2-TX1+-PadA2)") (class "Default")
      (node (ref "J2") (pin "A2") (pinfunction "TX1+_A2") (pintype "passive"))
    )
    (net (code "66") (name "unconnected-(J2-TX1--PadA3)") (class "Default")
      (node (ref "J2") (pin "A3") (pinfunction "TX1-_A3") (pintype "passive"))
    )
    (net (code "67") (name "unconnected-(J2-TX2+-PadB2)") (class "Default")
      (node (ref "J2") (pin "B2") (pinfunction "TX2+_B2") (pintype "passive"))
    )
    (net (code "68") (name "unconnected-(J2-TX2--PadB3)") (class "Default")
      (node (ref "J2") (pin "B3") (pinfunction "TX2-_B3") (pintype "passive"))
    )
    (net (code "69") (name "unconnected-(PAD1-P-Pad1)") (class "Default")
      (node (ref "PAD1") (pin "1") (pinfunction "P_1") (pintype "passive"))
    )
    (net (code "70") (name "unconnected-(PAD2-P-Pad1)") (class "Default")
      (node (ref "PAD2") (pin "1") (pinfunction "P_1") (pintype "passive"))
    )
    (net (code "71") (name "unconnected-(U$1-Pad17)") (class "Default")
      (node (ref "U$1") (pin "17") (pinfunction "17_17") (pintype "bidirectional"))
    )
    (net (code "72") (name "unconnected-(U$2-Pad22)") (class "Default")
      (node (ref "U$2") (pin "22") (pinfunction "22_22") (pintype "bidirectional"))
    )
    (net (code "73") (name "unconnected-(U1-IO2-Pad24)") (class "Default")
      (node (ref "U1") (pin "24") (pinfunction "IO2_24") (pintype "bidirectional"))
    )
    (net (code "74") (name "unconnected-(U1-IO15-Pad23)") (class "Default")
      (node (ref "U1") (pin "23") (pinfunction "IO15_23") (pintype "bidirectional"))
    )
    (net (code "75") (name "unconnected-(U1-IO35-Pad7)") (class "Default")
      (node (ref "U1") (pin "7") (pinfunction "IO35_7") (pintype "input"))
    )
    (net (code "76") (name "unconnected-(U1-SCK{slash}CLK-Pad20)") (class "Default")
      (node (ref "U1") (pin "20") (pinfunction "SCK/CLK_20") (pintype "bidirectional"))
    )
    (net (code "77") (name "unconnected-(U1-SCS{slash}CMD-Pad19)") (class "Default")
      (node (ref "U1") (pin "19") (pinfunction "SCS/CMD_19") (pintype "bidirectional"))
    )
    (net (code "78") (name "unconnected-(U1-SDI{slash}SD1-Pad22)") (class "Default")
      (node (ref "U1") (pin "22") (pinfunction "SDI/SD1_22") (pintype "bidirectional"))
    )
    (net (code "79") (name "unconnected-(U1-SDO{slash}SD0-Pad21)") (class "Default")
      (node (ref "U1") (pin "21") (pinfunction "SDO/SD0_21") (pintype "bidirectional"))
    )
    (net (code "80") (name "unconnected-(U1-SHD{slash}SD2-Pad17)") (class "Default")
      (node (ref "U1") (pin "17") (pinfunction "SHD/SD2_17") (pintype "bidirectional"))
    )
    (net (code "81") (name "unconnected-(U1-SWP{slash}SD3-Pad18)") (class "Default")
      (node (ref "U1") (pin "18") (pinfunction "SWP/SD3_18") (pintype "bidirectional"))
    )
    (net (code "82") (name "unconnected-(U2-CTS-Pad18)") (class "Default")
      (node (ref "U2") (pin "18") (pinfunction "CTS_18") (pintype "input"))
    )
    (net (code "83") (name "unconnected-(U2-DCD-Pad24)") (class "Default")
      (node (ref "U2") (pin "24") (pinfunction "DCD_24") (pintype "bidirectional"))
    )
    (net (code "84") (name "unconnected-(U2-DSR-Pad22)") (class "Default")
      (node (ref "U2") (pin "22") (pinfunction "DSR_22") (pintype "bidirectional"))
    )
    (net (code "85") (name "unconnected-(U2-GPIO.0{slash}TXT-Pad14)") (class "Default")
      (node (ref "U2") (pin "14") (pinfunction "GPIO.0/TXT_14") (pintype "bidirectional"))
    )
    (net (code "86") (name "unconnected-(U2-GPIO.1{slash}RXT-Pad13)") (class "Default")
      (node (ref "U2") (pin "13") (pinfunction "GPIO.1/RXT_13") (pintype "bidirectional"))
    )
    (net (code "87") (name "unconnected-(U2-GPIO.2{slash}RS485-Pad12)") (class "Default")
      (node (ref "U2") (pin "12") (pinfunction "GPIO.2/RS485_12") (pintype "bidirectional"))
    )
    (net (code "88") (name "unconnected-(U2-GPIO.3{slash}WAKEUP-Pad11)") (class "Default")
      (node (ref "U2") (pin "11") (pinfunction "GPIO.3/WAKEUP_11") (pintype "bidirectional"))
    )
    (net (code "89") (name "unconnected-(U2-RI{slash}CLK-Pad1)") (class "Default")
      (node (ref "U2") (pin "1") (pinfunction "RI/CLK_1") (pintype "input"))
    )
    (net (code "90") (name "unconnected-(U2-SUSPEND-Pad17)") (class "Default")
      (node (ref "U2") (pin "17") (pinfunction "SUSPEND_17") (pintype "output"))
    )
    (net (code "91") (name "unconnected-(U2-VIO-Pad5)") (class "Default")
      (node (ref "U2") (pin "5") (pinfunction "VIO_5") (pintype "bidirectional"))
    )
    (net (code "92") (name "unconnected-(U2-~{SUSPEND}-Pad15)") (class "Default")
      (node (ref "U2") (pin "15") (pinfunction "~{SUSPEND}_15") (pintype "output"))
    )
  )
)
